# GWLSensorv4.net
KiCad netlist of a schematic drawn in EAGLE
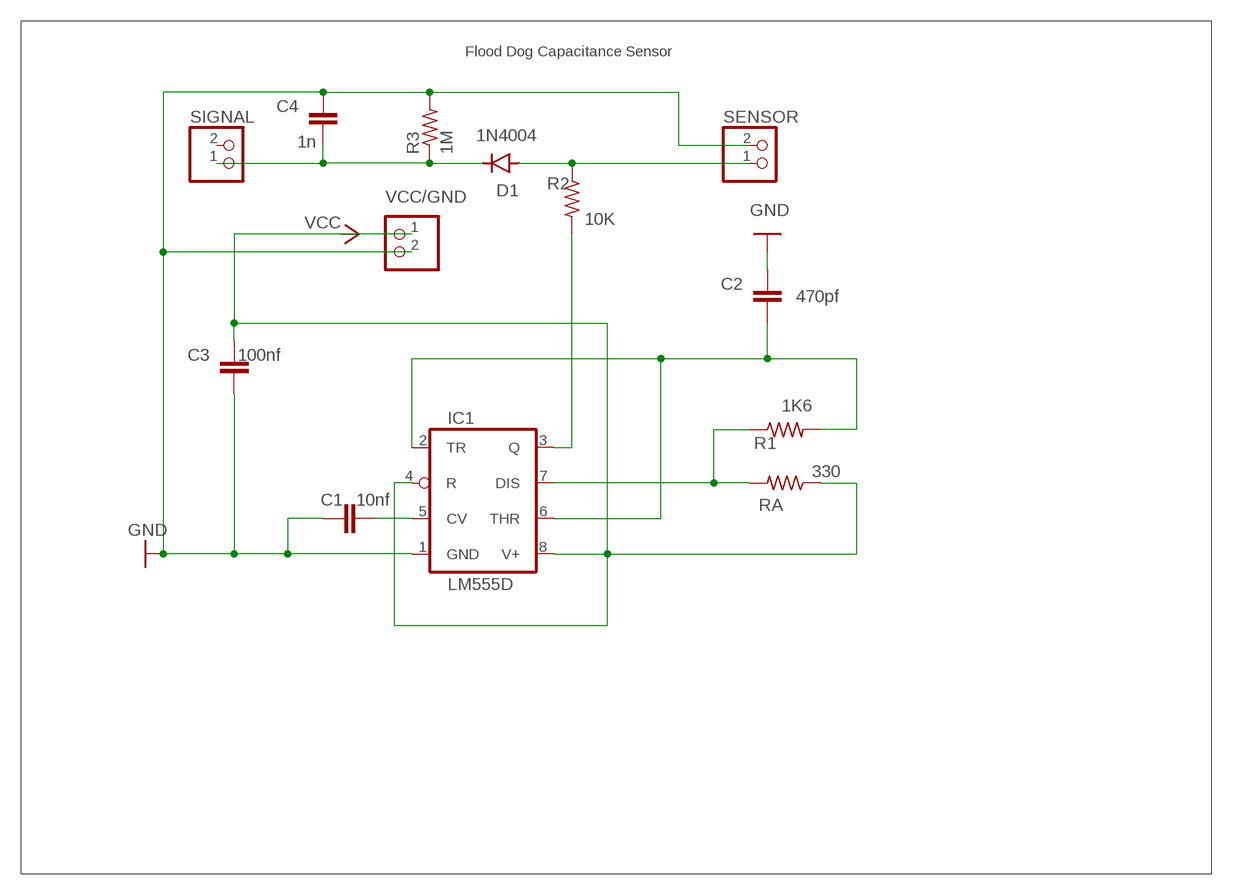
[diagram p0: schematic, sheet 1]

(export (version "E")
  (design (tool "Eeschema 10.0.6"))
  (components
    (comp (ref "C1")
      (value "10nf")
      (footprint "eagle-import:C0805")
      (libsource (lib "eagle-import") (part "C-EUC0805"))
    )
    (comp (ref "C2")
      (value "470pf")
      (footprint "eagle-import:C0805")
      (libsource (lib "eagle-import") (part "C-EUC0805"))
    )
    (comp (ref "C3")
      (value "100nf")
      (footprint "eagle-import:C0805")
      (libsource (lib "eagle-import") (part "C-EUC0805"))
    )
    (comp (ref "C4")
      (value "1n")
      (footprint "eagle-import:C0805")
      (libsource (lib "eagle-import") (part "C-EUC0805"))
    )
    (comp (ref "D1")
      (value "1N4004")
      (footprint "eagle-import:DO41-10")
      (libsource (lib "eagle-import") (part "1N4004"))
    )
    (comp (ref "IC1")
      (value "LM555D")
      (footprint "eagle-import:SO08")
      (libsource (lib "eagle-import") (part "555DLM"))
    )
    (comp (ref "R1")
      (value "1K6")
      (footprint "eagle-import:R0805")
      (libsource (lib "eagle-import") (part "R-US_R0805"))
    )
    (comp (ref "R2")
      (value "10K")
      (footprint "eagle-import:R0805")
      (libsource (lib "eagle-import") (part "R-US_R0805"))
    )
    (comp (ref "R3")
      (value "1M")
      (footprint "eagle-import:R0805")
      (libsource (lib "eagle-import") (part "R-US_R0805"))
    )
    (comp (ref "RA")
      (value "330")
      (footprint "eagle-import:R0805")
      (libsource (lib "eagle-import") (part "R-US_R0805"))
    )
    (comp (ref "SENSOR")
      (value "JST_2PIN-SMT")
      (footprint "eagle-import:JST-PH-2-SMT")
      (libsource (lib "eagle-import") (part "JST_2PIN-SMT"))
    )
    (comp (ref "SIGNAL")
      (value "JST_2PIN-SMT")
      (footprint "eagle-import:JST-PH-2-SMT")
      (libsource (lib "eagle-import") (part "JST_2PIN-SMT"))
    )
    (comp (ref "VCC/GND")
      (value "JST_2PIN-SMT")
      (footprint "eagle-import:JST-PH-2-SMT")
      (libsource (lib "eagle-import") (part "JST_2PIN-SMT"))
    )
  )
  (nets
    (net (code "1") (name "GND") (class "Default")
      (node (ref "C1") (pin "1") (pinfunction "1_1") (pintype "passive"))
      (node (ref "C2") (pin "2") (pinfunction "2_2") (pintype "passive"))
      (node (ref "C3") (pin "1") (pinfunction "1_1") (pintype "passive"))
      (node (ref "C4") (pin "2") (pinfunction "2_2") (pintype "passive"))
      (node (ref "IC1") (pin "1") (pinfunction "GND_1") (pintype "power_in"))
      (node (ref "R3") (pin "2") (pinfunction "2_2") (pintype "passive"))
      (node (ref "SENSOR") (pin "2") (pinfunction "1_2") (pintype "passive"))
      (node (ref "VCC/GND") (pin "2") (pinfunction "1_2") (pintype "passive"))
    )
    (net (code "2") (name "Net-(IC1-CV)") (class "Default")
      (node (ref "C1") (pin "2") (pinfunction "2_2") (pintype "passive"))
      (node (ref "IC1") (pin "5") (pinfunction "CV_5") (pintype "input"))
    )
    (net (code "3") (name "Net-(IC1-DIS)") (class "Default")
      (node (ref "IC1") (pin "7") (pinfunction "DIS_7") (pintype "input"))
      (node (ref "R1") (pin "1") (pinfunction "1_1") (pintype "passive"))
      (node (ref "RA") (pin "2") (pinfunction "2_2") (pintype "passive"))
    )
    (net (code "4") (name "Net-(IC1-Q)") (class "Default")
      (node (ref "IC1") (pin "3") (pinfunction "Q_3") (pintype "output"))
      (node (ref "R2") (pin "2") (pinfunction "2_2") (pintype "passive"))
    )
    (net (code "5") (name "Net-(IC1-THR)") (class "Default")
      (node (ref "C2") (pin "1") (pinfunction "1_1") (pintype "passive"))
      (node (ref "IC1") (pin "2") (pinfunction "TR_2") (pintype "input"))
      (node (ref "IC1") (pin "6") (pinfunction "THR_6") (pintype "input"))
      (node (ref "R1") (pin "2") (pinfunction "2_2") (pintype "passive"))
    )
    (net (code "6") (name "Net-(SENSOR-2)") (class "Default")
      (node (ref "D1") (pin "A") (pinfunction "A_A") (pintype "passive"))
      (node (ref "R2") (pin "1") (pinfunction "1_1") (pintype "passive"))
      (node (ref "SENSOR") (pin "1") (pinfunction "2_1") (pintype "passive"))
    )
    (net (code "7") (name "Net-(SIGNAL-2)") (class "Default")
      (node (ref "C4") (pin "1") (pinfunction "1_1") (pintype "passive"))
      (node (ref "D1") (pin "C") (pinfunction "C_C") (pintype "passive"))
      (node (ref "R3") (pin "1") (pinfunction "1_1") (pintype "passive"))
      (node (ref "SIGNAL") (pin "1") (pinfunction "2_1") (pintype "passive"))
    )
    (net (code "8") (name "VCC") (class "Default")
      (node (ref "C3") (pin "2") (pinfunction "2_2") (pintype "passive"))
      (node (ref "IC1") (pin "4") (pinfunction "R_4") (pintype "input"))
      (node (ref "IC1") (pin "8") (pinfunction "V+_8") (pintype "power_in"))
      (node (ref "RA") (pin "1") (pinfunction "1_1") (pintype "passive"))
      (node (ref "VCC/GND") (pin "1") (pinfunction "2_1") (pintype "passive"))
    )
    (net (code "9") (name "unconnected-(SIGNAL-1-Pad2)") (class "Default")
      (node (ref "SIGNAL") (pin "2") (pinfunction "1_2") (pintype "passive"))
    )
  )
)
